# M_H_ext_rgb.net
KiCad netlist of a schematic drawn in EAGLE
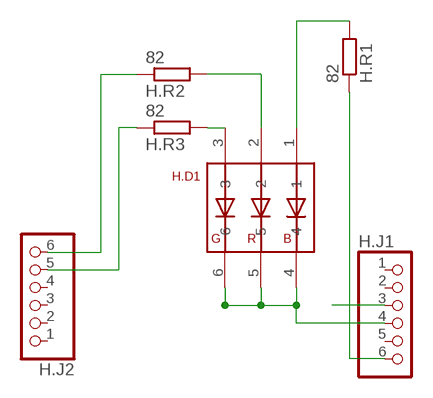
[diagram p0: schematic, sheet 1]

(export (version "E")
  (design (tool "Eeschema 10.0.6"))
  (components
    (comp (ref "H.D1")
      (value "RGB_WW-FCE50TC-Q1")
      (footprint "eagle-import:RGB_WW-FCE50TC-Q1")
      (libsource (lib "eagle-import") (part "RGB_WW-FCE50TC-Q1"))
    )
    (comp (ref "H.J1")
      (value "PINHD-1X6")
      (footprint "eagle-import:1X06")
      (libsource (lib "eagle-import") (part "PINHD-1X6"))
    )
    (comp (ref "H.J2")
      (value "PINHD-1X6")
      (footprint "eagle-import:1X06")
      (libsource (lib "eagle-import") (part "PINHD-1X6"))
    )
    (comp (ref "H.R1")
      (value "82")
      (footprint "eagle-import:R0603")
      (libsource (lib "eagle-import") (part "R-EU_R0603"))
    )
    (comp (ref "H.R2")
      (value "82")
      (footprint "eagle-import:R0603")
      (libsource (lib "eagle-import") (part "R-EU_R0603"))
    )
    (comp (ref "H.R3")
      (value "82")
      (footprint "eagle-import:R0603")
      (libsource (lib "eagle-import") (part "R-EU_R0603"))
    )
  )
  (nets
    (net (code "1") (name "Net-(H.D1-Pad1)") (class "Default")
      (node (ref "H.D1") (pin "1") (pinfunction "1_1") (pintype "bidirectional"))
      (node (ref "H.R1") (pin "2") (pinfunction "2_2") (pintype "passive"))
    )
    (net (code "2") (name "Net-(H.D1-Pad2)") (class "Default")
      (node (ref "H.D1") (pin "2") (pinfunction "2_2") (pintype "bidirectional"))
      (node (ref "H.R2") (pin "2") (pinfunction "2_2") (pintype "passive"))
    )
    (net (code "3") (name "Net-(H.D1-Pad3)") (class "Default")
      (node (ref "H.D1") (pin "3") (pinfunction "3_3") (pintype "bidirectional"))
      (node (ref "H.R3") (pin "2") (pinfunction "2_2") (pintype "passive"))
    )
    (net (code "4") (name "Net-(H.D1-Pad4)") (class "Default")
      (node (ref "H.D1") (pin "4") (pinfunction "4_4") (pintype "bidirectional"))
      (node (ref "H.D1") (pin "5") (pinfunction "5_5") (pintype "bidirectional"))
      (node (ref "H.D1") (pin "6") (pinfunction "6_6") (pintype "bidirectional"))
      (node (ref "H.J1") (pin "4") (pinfunction "4_4") (pintype "passive"))
    )
    (net (code "5") (name "Net-(H.J1-Pad6)") (class "Default")
      (node (ref "H.J1") (pin "6") (pinfunction "6_6") (pintype "passive"))
      (node (ref "H.R1") (pin "1") (pinfunction "1_1") (pintype "passive"))
    )
    (net (code "6") (name "Net-(H.J2-Pad5)") (class "Default")
      (node (ref "H.J2") (pin "5") (pinfunction "5_5") (pintype "passive"))
      (node (ref "H.R3") (pin "1") (pinfunction "1_1") (pintype "passive"))
    )
    (net (code "7") (name "Net-(H.J2-Pad6)") (class "Default")
      (node (ref "H.J2") (pin "6") (pinfunction "6_6") (pintype "passive"))
      (node (ref "H.R2") (pin "1") (pinfunction "1_1") (pintype "passive"))
    )
    (net (code "8") (name "unconnected-(H.J1-Pad1)") (class "Default")
      (node (ref "H.J1") (pin "1") (pinfunction "1_1") (pintype "passive"))
    )
    (net (code "9") (name "unconnected-(H.J1-Pad2)") (class "Default")
      (node (ref "H.J1") (pin "2") (pinfunction "2_2") (pintype "passive"))
    )
    (net (code "10") (name "unconnected-(H.J1-Pad3)") (class "Default")
      (node (ref "H.J1") (pin "3") (pinfunction "3_3") (pintype "passive"))
    )
    (net (code "11") (name "unconnected-(H.J1-Pad5)") (class "Default")
      (node (ref "H.J1") (pin "5") (pinfunction "5_5") (pintype "passive"))
    )
    (net (code "12") (name "unconnected-(H.J2-Pad1)") (class "Default")
      (node (ref "H.J2") (pin "1") (pinfunction "1_1") (pintype "passive"))
    )
    (net (code "13") (name "unconnected-(H.J2-Pad2)") (class "Default")
      (node (ref "H.J2") (pin "2") (pinfunction "2_2") (pintype "passive"))
    )
    (net (code "14") (name "unconnected-(H.J2-Pad3)") (class "Default")
      (node (ref "H.J2") (pin "3") (pinfunction "3_3") (pintype "passive"))
    )
    (net (code "15") (name "unconnected-(H.J2-Pad4)") (class "Default")
      (node (ref "H.J2") (pin "4") (pinfunction "4_4") (pintype "passive"))
    )
  )
)
